# TeslaBMS_Shield_3.net
KiCad netlist of a schematic drawn in EAGLE
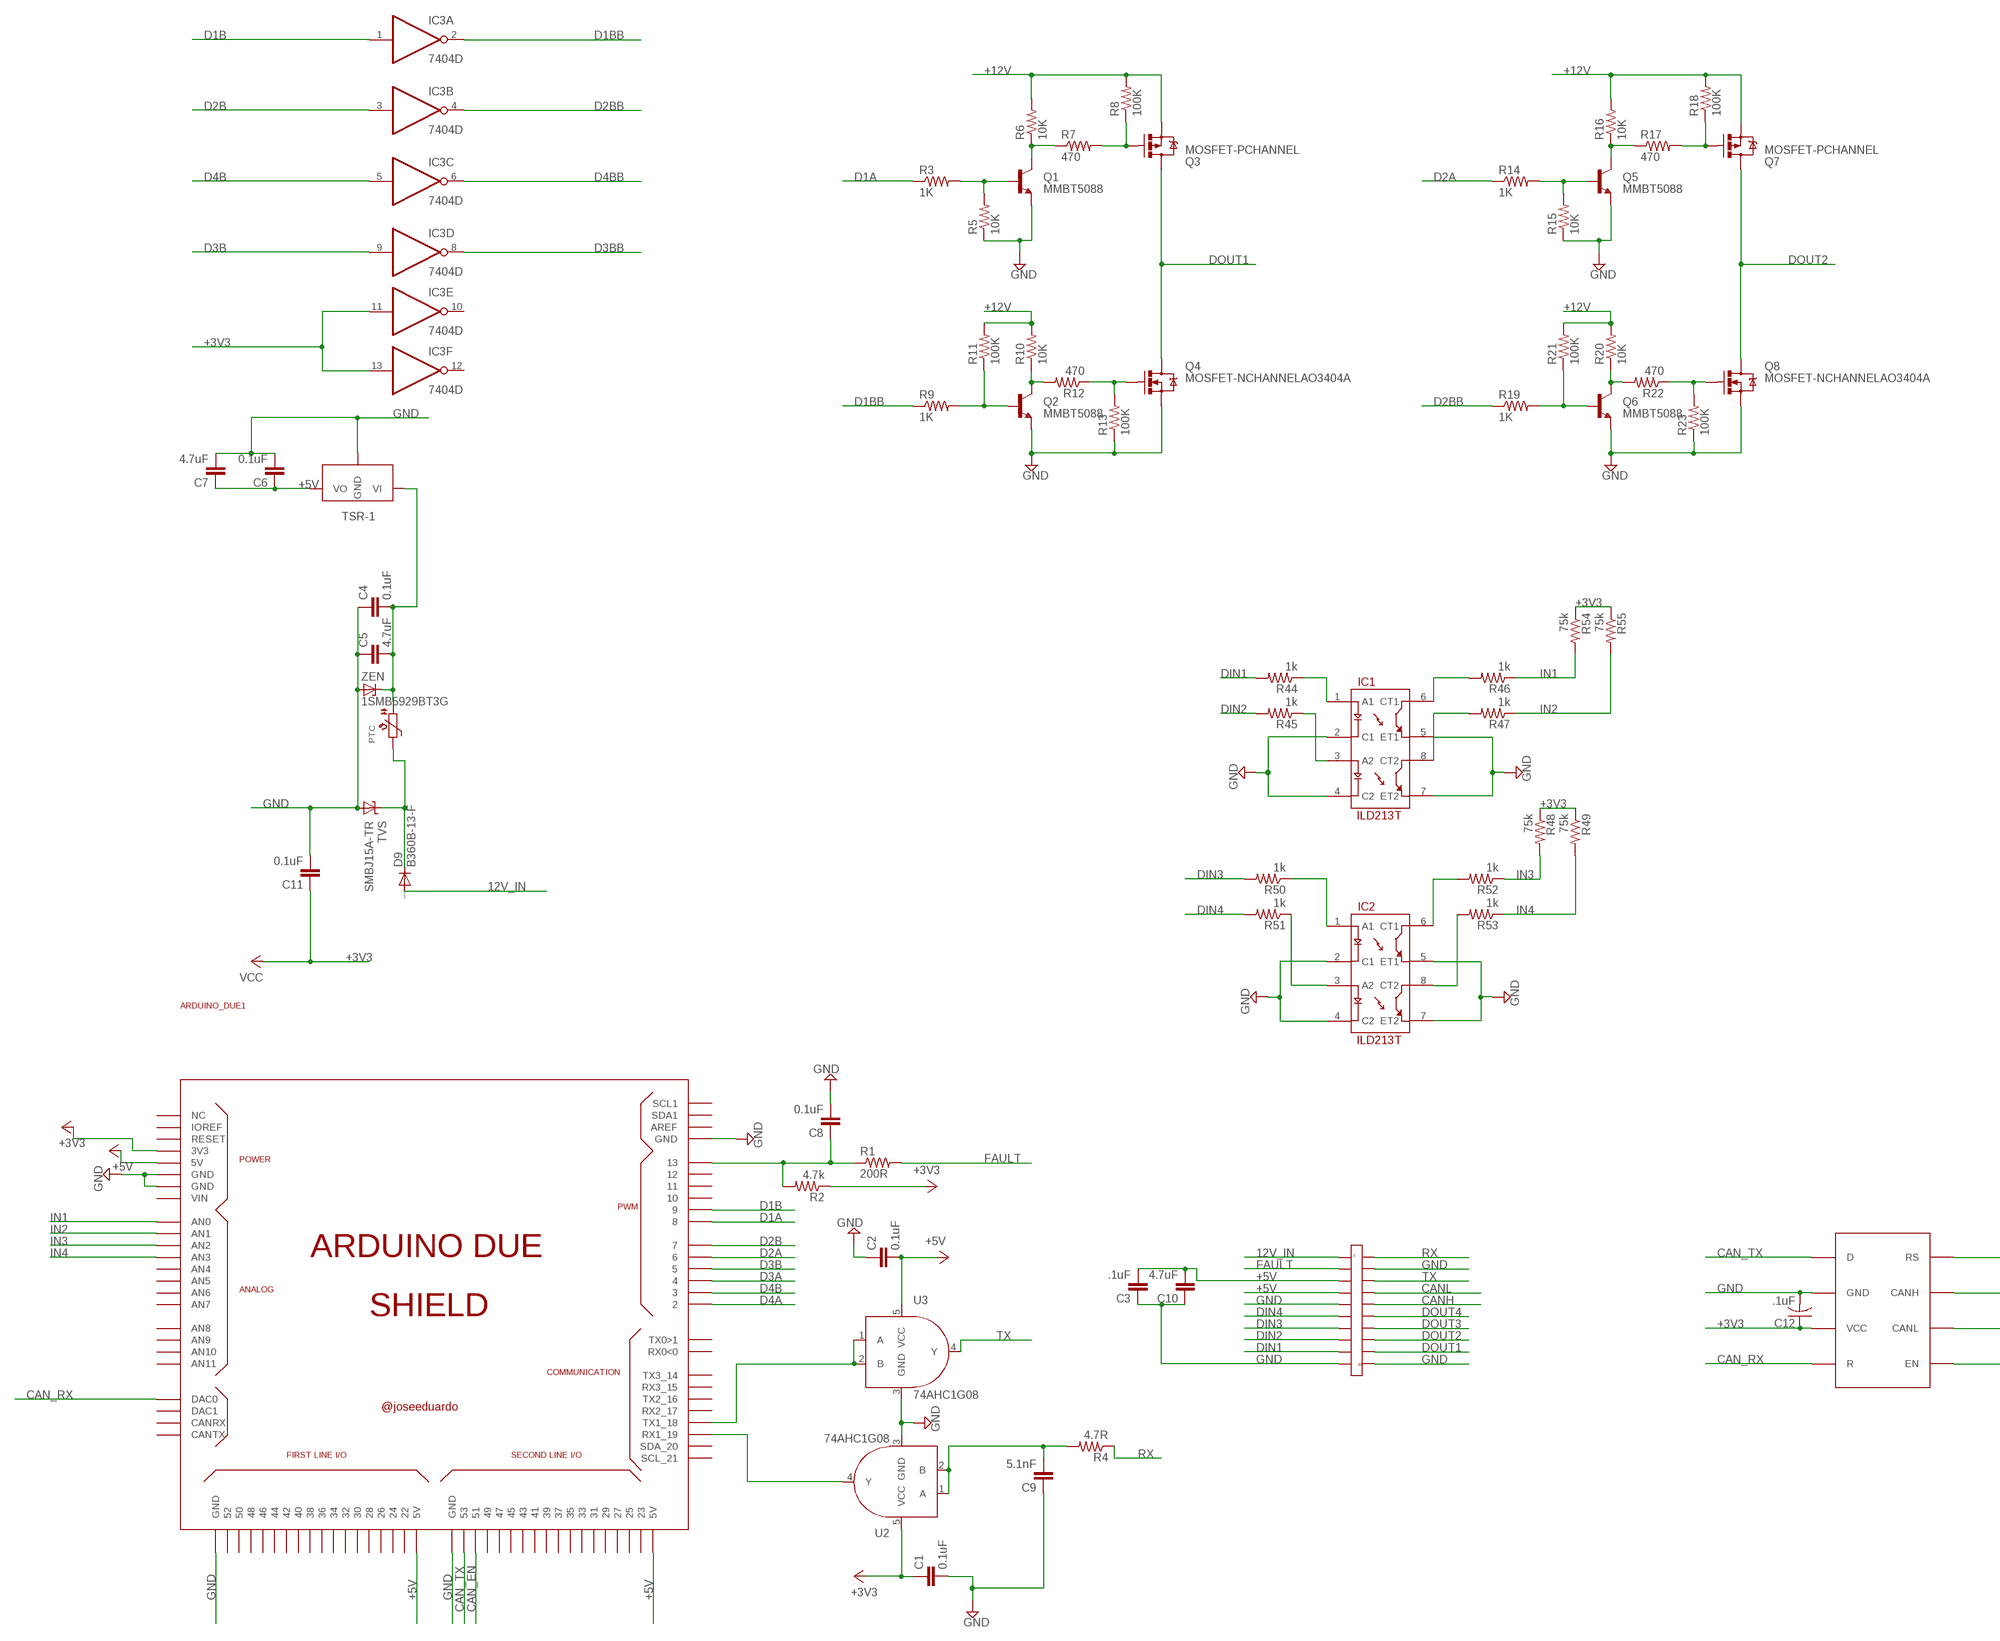
[diagram p0: schematic, sheet 1, part 1 of 2]
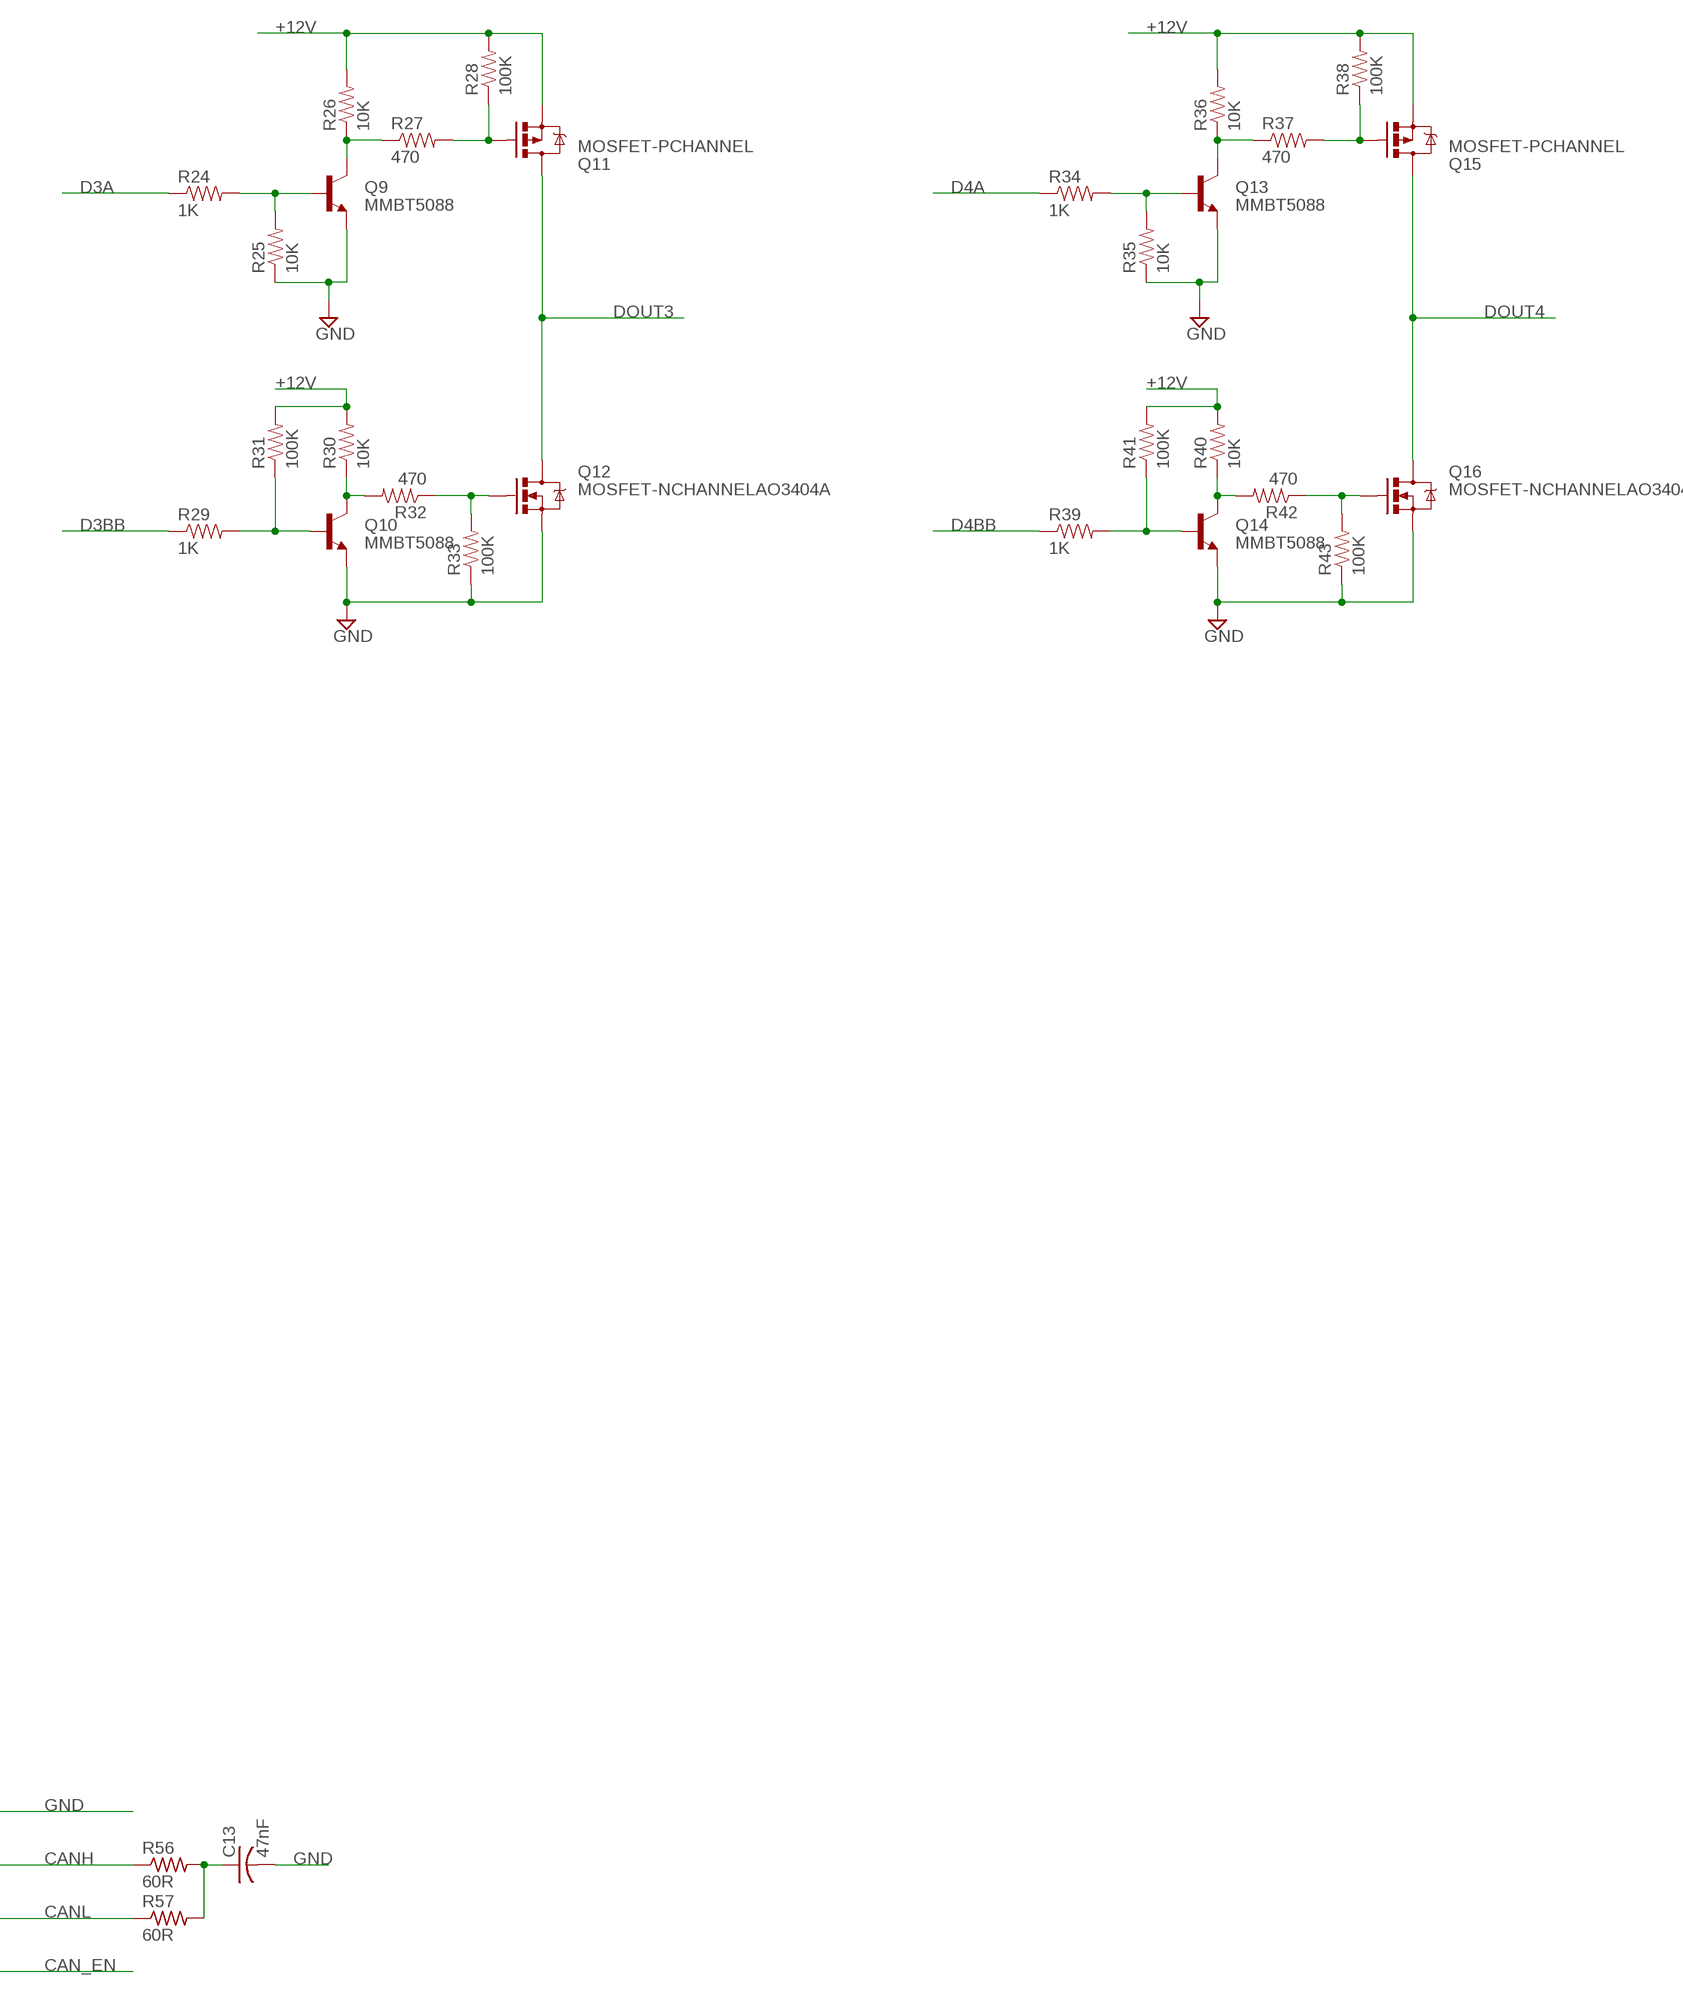
[diagram p1: schematic, sheet 1, part 2 of 2]

(export (version "E")
  (design (tool "Eeschema 10.0.6"))
  (components
    (comp (ref "ARDUINO_DUE1")
      (value "ARDUINO_DUE_SHIELD")
      (footprint "eagle-import:ARDUINO_DUE_SHIELD")
      (libsource (lib "eagle-import") (part "ARDUINO_DUE_SHIELD"))
    )
    (comp (ref "C1")
      (value "0.1uF")
      (footprint "eagle-import:0603-CAP")
      (libsource (lib "eagle-import") (part "CAP0603-CAP"))
    )
    (comp (ref "C2")
      (value "0.1uF")
      (footprint "eagle-import:0603-CAP")
      (libsource (lib "eagle-import") (part "CAP0603-CAP"))
    )
    (comp (ref "C3")
      (value ".1uF")
      (footprint "eagle-import:0603-CAP")
      (libsource (lib "eagle-import") (part "CAP0603-CAP"))
    )
    (comp (ref "C4")
      (value "0.1uF")
      (footprint "eagle-import:0805")
      (libsource (lib "eagle-import") (part "CAP0805"))
    )
    (comp (ref "C5")
      (value "4.7uF")
      (footprint "eagle-import:0805")
      (libsource (lib "eagle-import") (part "CAP0805"))
    )
    (comp (ref "C6")
      (value "0.1uF")
      (footprint "eagle-import:0805")
      (libsource (lib "eagle-import") (part "CAP0805"))
    )
    (comp (ref "C7")
      (value "4.7uF")
      (footprint "eagle-import:0805")
      (libsource (lib "eagle-import") (part "CAP0805"))
    )
    (comp (ref "C8")
      (value "0.1uF")
      (footprint "eagle-import:0603-CAP")
      (libsource (lib "eagle-import") (part "CAP0603-CAP"))
    )
    (comp (ref "C9")
      (value "5.1nF")
      (footprint "eagle-import:0603-CAP")
      (libsource (lib "eagle-import") (part "CAP0603-CAP"))
    )
    (comp (ref "C10")
      (value "4.7uF")
      (footprint "eagle-import:0603-CAP")
      (libsource (lib "eagle-import") (part "CAP0603-CAP"))
    )
    (comp (ref "C11")
      (value "0.1uF")
      (footprint "eagle-import:0805")
      (libsource (lib "eagle-import") (part "CAP0805"))
    )
    (comp (ref "C12")
      (value ".1uF")
      (footprint "eagle-import:C0603")
      (libsource (lib "eagle-import") (part "C-USC0603"))
    )
    (comp (ref "C13")
      (value "47nF")
      (footprint "eagle-import:C0805")
      (libsource (lib "eagle-import") (part "C-USC0805"))
    )
    (comp (ref "D9")
      (value "B360B-13-F")
      (footprint "eagle-import:SMB")
      (libsource (lib "eagle-import") (part "DIODE-SMB"))
    )
    (comp (ref "IC1")
      (value "ILD213T")
      (footprint "eagle-import:SO08")
      (libsource (lib "eagle-import") (part "ILD213T"))
    )
    (comp (ref "IC2")
      (value "ILD213T")
      (footprint "eagle-import:SO08")
      (libsource (lib "eagle-import") (part "ILD213T"))
    )
    (comp (ref "IC3")
      (value "7404D")
      (footprint "eagle-import:SO14")
      (libsource (lib "eagle-import") (part "7404D"))
    )
    (comp (ref "PTC")
      (value "PTC1812")
      (footprint "eagle-import:PTC1812")
      (libsource (lib "eagle-import") (part "PTC1812"))
    )
    (comp (ref "Q1")
      (value "MMBT5088")
      (footprint "eagle-import:SOT23-3")
      (libsource (lib "eagle-import") (part "TRANSISTOR_NPNMMBT5088"))
    )
    (comp (ref "Q2")
      (value "MMBT5088")
      (footprint "eagle-import:SOT23-3")
      (libsource (lib "eagle-import") (part "TRANSISTOR_NPNMMBT5088"))
    )
    (comp (ref "Q3")
      (value "MOSFET-PCHANNEL")
      (footprint "eagle-import:SOT23-3")
      (libsource (lib "eagle-import") (part "MOSFET-PCHANNEL"))
    )
    (comp (ref "Q4")
      (value "MOSFET-NCHANNELAO3404A")
      (footprint "eagle-import:SOT23-3")
      (libsource (lib "eagle-import") (part "MOSFET-NCHANNELAO3404A"))
    )
    (comp (ref "Q5")
      (value "MMBT5088")
      (footprint "eagle-import:SOT23-3")
      (libsource (lib "eagle-import") (part "TRANSISTOR_NPNMMBT5088"))
    )
    (comp (ref "Q6")
      (value "MMBT5088")
      (footprint "eagle-import:SOT23-3")
      (libsource (lib "eagle-import") (part "TRANSISTOR_NPNMMBT5088"))
    )
    (comp (ref "Q7")
      (value "MOSFET-PCHANNEL")
      (footprint "eagle-import:SOT23-3")
      (libsource (lib "eagle-import") (part "MOSFET-PCHANNEL"))
    )
    (comp (ref "Q8")
      (value "MOSFET-NCHANNELAO3404A")
      (footprint "eagle-import:SOT23-3")
      (libsource (lib "eagle-import") (part "MOSFET-NCHANNELAO3404A"))
    )
    (comp (ref "Q9")
      (value "MMBT5088")
      (footprint "eagle-import:SOT23-3")
      (libsource (lib "eagle-import") (part "TRANSISTOR_NPNMMBT5088"))
    )
    (comp (ref "Q10")
      (value "MMBT5088")
      (footprint "eagle-import:SOT23-3")
      (libsource (lib "eagle-import") (part "TRANSISTOR_NPNMMBT5088"))
    )
    (comp (ref "Q11")
      (value "MOSFET-PCHANNEL")
      (footprint "eagle-import:SOT23-3")
      (libsource (lib "eagle-import") (part "MOSFET-PCHANNEL"))
    )
    (comp (ref "Q12")
      (value "MOSFET-NCHANNELAO3404A")
      (footprint "eagle-import:SOT23-3")
      (libsource (lib "eagle-import") (part "MOSFET-NCHANNELAO3404A"))
    )
    (comp (ref "Q13")
      (value "MMBT5088")
      (footprint "eagle-import:SOT23-3")
      (libsource (lib "eagle-import") (part "TRANSISTOR_NPNMMBT5088"))
    )
    (comp (ref "Q14")
      (value "MMBT5088")
      (footprint "eagle-import:SOT23-3")
      (libsource (lib "eagle-import") (part "TRANSISTOR_NPNMMBT5088"))
    )
    (comp (ref "Q15")
      (value "MOSFET-PCHANNEL")
      (footprint "eagle-import:SOT23-3")
      (libsource (lib "eagle-import") (part "MOSFET-PCHANNEL"))
    )
    (comp (ref "Q16")
      (value "MOSFET-NCHANNELAO3404A")
      (footprint "eagle-import:SOT23-3")
      (libsource (lib "eagle-import") (part "MOSFET-NCHANNELAO3404A"))
    )
    (comp (ref "R1")
      (value "200R")
      (footprint "eagle-import:0603-RES")
      (libsource (lib "eagle-import") (part "RESISTOR0603-RES"))
    )
    (comp (ref "R2")
      (value "4.7k")
      (footprint "eagle-import:0603-RES")
      (libsource (lib "eagle-import") (part "RESISTOR0603-RES"))
    )
    (comp (ref "R3")
      (value "1K")
      (footprint "eagle-import:0402-RES")
      (libsource (lib "eagle-import") (part "RESISTOR0402"))
    )
    (comp (ref "R4")
      (value "4.7R")
      (footprint "eagle-import:0603-RES")
      (libsource (lib "eagle-import") (part "RESISTOR0603-RES"))
    )
    (comp (ref "R5")
      (value "10K")
      (footprint "eagle-import:0402-RES")
      (libsource (lib "eagle-import") (part "RESISTOR0402"))
    )
    (comp (ref "R6")
      (value "10K")
      (footprint "eagle-import:0402-RES")
      (libsource (lib "eagle-import") (part "RESISTOR0402"))
    )
    (comp (ref "R7")
      (value "470")
      (footprint "eagle-import:0402-RES")
      (libsource (lib "eagle-import") (part "RESISTOR0402"))
    )
    (comp (ref "R8")
      (value "100K")
      (footprint "eagle-import:0402-RES")
      (libsource (lib "eagle-import") (part "RESISTOR0402"))
    )
    (comp (ref "R9")
      (value "1K")
      (footprint "eagle-import:0402-RES")
      (libsource (lib "eagle-import") (part "RESISTOR0402"))
    )
    (comp (ref "R10")
      (value "10K")
      (footprint "eagle-import:0402-RES")
      (libsource (lib "eagle-import") (part "RESISTOR0402"))
    )
    (comp (ref "R11")
      (value "100K")
      (footprint "eagle-import:0402-RES")
      (libsource (lib "eagle-import") (part "RESISTOR0402"))
    )
    (comp (ref "R12")
      (value "470")
      (footprint "eagle-import:0402-RES")
      (libsource (lib "eagle-import") (part "RESISTOR0402"))
    )
    (comp (ref "R13")
      (value "100K")
      (footprint "eagle-import:0402-RES")
      (libsource (lib "eagle-import") (part "RESISTOR0402"))
    )
    (comp (ref "R14")
      (value "1K")
      (footprint "eagle-import:0402-RES")
      (libsource (lib "eagle-import") (part "RESISTOR0402"))
    )
    (comp (ref "R15")
      (value "10K")
      (footprint "eagle-import:0402-RES")
      (libsource (lib "eagle-import") (part "RESISTOR0402"))
    )
    (comp (ref "R16")
      (value "10K")
      (footprint "eagle-import:0402-RES")
      (libsource (lib "eagle-import") (part "RESISTOR0402"))
    )
    (comp (ref "R17")
      (value "470")
      (footprint "eagle-import:0402-RES")
      (libsource (lib "eagle-import") (part "RESISTOR0402"))
    )
    (comp (ref "R18")
      (value "100K")
      (footprint "eagle-import:0402-RES")
      (libsource (lib "eagle-import") (part "RESISTOR0402"))
    )
    (comp (ref "R19")
      (value "1K")
      (footprint "eagle-import:0402-RES")
      (libsource (lib "eagle-import") (part "RESISTOR0402"))
    )
    (comp (ref "R20")
      (value "10K")
      (footprint "eagle-import:0402-RES")
      (libsource (lib "eagle-import") (part "RESISTOR0402"))
    )
    (comp (ref "R21")
      (value "100K")
      (footprint "eagle-import:0402-RES")
      (libsource (lib "eagle-import") (part "RESISTOR0402"))
    )
    (comp (ref "R22")
      (value "470")
      (footprint "eagle-import:0402-RES")
      (libsource (lib "eagle-import") (part "RESISTOR0402"))
    )
    (comp (ref "R23")
      (value "100K")
      (footprint "eagle-import:0402-RES")
      (libsource (lib "eagle-import") (part "RESISTOR0402"))
    )
    (comp (ref "R24")
      (value "1K")
      (footprint "eagle-import:0402-RES")
      (libsource (lib "eagle-import") (part "RESISTOR0402"))
    )
    (comp (ref "R25")
      (value "10K")
      (footprint "eagle-import:0402-RES")
      (libsource (lib "eagle-import") (part "RESISTOR0402"))
    )
    (comp (ref "R26")
      (value "10K")
      (footprint "eagle-import:0402-RES")
      (libsource (lib "eagle-import") (part "RESISTOR0402"))
    )
    (comp (ref "R27")
      (value "470")
      (footprint "eagle-import:0402-RES")
      (libsource (lib "eagle-import") (part "RESISTOR0402"))
    )
    (comp (ref "R28")
      (value "100K")
      (footprint "eagle-import:0402-RES")
      (libsource (lib "eagle-import") (part "RESISTOR0402"))
    )
    (comp (ref "R29")
      (value "1K")
      (footprint "eagle-import:0402-RES")
      (libsource (lib "eagle-import") (part "RESISTOR0402"))
    )
    (comp (ref "R30")
      (value "10K")
      (footprint "eagle-import:0402-RES")
      (libsource (lib "eagle-import") (part "RESISTOR0402"))
    )
    (comp (ref "R31")
      (value "100K")
      (footprint "eagle-import:0402-RES")
      (libsource (lib "eagle-import") (part "RESISTOR0402"))
    )
    (comp (ref "R32")
      (value "470")
      (footprint "eagle-import:0402-RES")
      (libsource (lib "eagle-import") (part "RESISTOR0402"))
    )
    (comp (ref "R33")
      (value "100K")
      (footprint "eagle-import:0402-RES")
      (libsource (lib "eagle-import") (part "RESISTOR0402"))
    )
    (comp (ref "R34")
      (value "1K")
      (footprint "eagle-import:0402-RES")
      (libsource (lib "eagle-import") (part "RESISTOR0402"))
    )
    (comp (ref "R35")
      (value "10K")
      (footprint "eagle-import:0402-RES")
      (libsource (lib "eagle-import") (part "RESISTOR0402"))
    )
    (comp (ref "R36")
      (value "10K")
      (footprint "eagle-import:0402-RES")
      (libsource (lib "eagle-import") (part "RESISTOR0402"))
    )
    (comp (ref "R37")
      (value "470")
      (footprint "eagle-import:0402-RES")
      (libsource (lib "eagle-import") (part "RESISTOR0402"))
    )
    (comp (ref "R38")
      (value "100K")
      (footprint "eagle-import:0402-RES")
      (libsource (lib "eagle-import") (part "RESISTOR0402"))
    )
    (comp (ref "R39")
      (value "1K")
      (footprint "eagle-import:0402-RES")
      (libsource (lib "eagle-import") (part "RESISTOR0402"))
    )
    (comp (ref "R40")
      (value "10K")
      (footprint "eagle-import:0402-RES")
      (libsource (lib "eagle-import") (part "RESISTOR0402"))
    )
    (comp (ref "R41")
      (value "100K")
      (footprint "eagle-import:0402-RES")
      (libsource (lib "eagle-import") (part "RESISTOR0402"))
    )
    (comp (ref "R42")
      (value "470")
      (footprint "eagle-import:0402-RES")
      (libsource (lib "eagle-import") (part "RESISTOR0402"))
    )
    (comp (ref "R43")
      (value "100K")
      (footprint "eagle-import:0402-RES")
      (libsource (lib "eagle-import") (part "RESISTOR0402"))
    )
    (comp (ref "R44")
      (value "1k")
      (footprint "eagle-import:0603-RES")
      (libsource (lib "eagle-import") (part "RESISTOR0603-RES"))
    )
    (comp (ref "R45")
      (value "1k")
      (footprint "eagle-import:0603-RES")
      (libsource (lib "eagle-import") (part "RESISTOR0603-RES"))
    )
    (comp (ref "R46")
      (value "1k")
      (footprint "eagle-import:0603-RES")
      (libsource (lib "eagle-import") (part "RESISTOR0603-RES"))
    )
    (comp (ref "R47")
      (value "1k")
      (footprint "eagle-import:0603-RES")
      (libsource (lib "eagle-import") (part "RESISTOR0603-RES"))
    )
    (comp (ref "R48")
      (value "75k")
      (footprint "eagle-import:0603-RES")
      (libsource (lib "eagle-import") (part "RESISTOR0603-RES"))
    )
    (comp (ref "R49")
      (value "75k")
      (footprint "eagle-import:0603-RES")
      (libsource (lib "eagle-import") (part "RESISTOR0603-RES"))
    )
    (comp (ref "R50")
      (value "1k")
      (footprint "eagle-import:0603-RES")
      (libsource (lib "eagle-import") (part "RESISTOR0603-RES"))
    )
    (comp (ref "R51")
      (value "1k")
      (footprint "eagle-import:0603-RES")
      (libsource (lib "eagle-import") (part "RESISTOR0603-RES"))
    )
    (comp (ref "R52")
      (value "1k")
      (footprint "eagle-import:0603-RES")
      (libsource (lib "eagle-import") (part "RESISTOR0603-RES"))
    )
    (comp (ref "R53")
      (value "1k")
      (footprint "eagle-import:0603-RES")
      (libsource (lib "eagle-import") (part "RESISTOR0603-RES"))
    )
    (comp (ref "R54")
      (value "75k")
      (footprint "eagle-import:0603-RES")
      (libsource (lib "eagle-import") (part "RESISTOR0603-RES"))
    )
    (comp (ref "R55")
      (value "75k")
      (footprint "eagle-import:0603-RES")
      (libsource (lib "eagle-import") (part "RESISTOR0603-RES"))
    )
    (comp (ref "R56")
      (value "60R")
      (footprint "eagle-import:M0805")
      (libsource (lib "eagle-import") (part "R-US_M0805"))
    )
    (comp (ref "R57")
      (value "60R")
      (footprint "eagle-import:M0805")
      (libsource (lib "eagle-import") (part "R-US_M0805"))
    )
    (comp (ref "TVS")
      (value "SMBJ15A-TR")
      (footprint "eagle-import:SMBJ")
      (libsource (lib "eagle-import") (part "SUPPRESSOR-SMBJ"))
    )
    (comp (ref "U$2")
      (value "VAL-U-LOK-20PIN")
      (footprint "eagle-import:VALULOK-20")
      (libsource (lib "eagle-import") (part "VAL-U-LOK-20PIN"))
    )
    (comp (ref "U1")
      (value "SN65HVD234")
      (footprint "eagle-import:SOIC8")
      (libsource (lib "eagle-import") (part "SN65HVD234"))
    )
    (comp (ref "U2")
      (value "74AHC1G08")
      (footprint "eagle-import:SOT353")
      (libsource (lib "eagle-import") (part "74AHC1G08"))
    )
    (comp (ref "U3")
      (value "74AHC1G08")
      (footprint "eagle-import:SOT353")
      (libsource (lib "eagle-import") (part "74AHC1G08"))
    )
    (comp (ref "U9")
      (value "TSR-1")
      (footprint "eagle-import:TSR-1")
      (libsource (lib "eagle-import") (part "TSR-1"))
    )
    (comp (ref "ZEN")
      (value "1SMB5929BT3G")
      (footprint "eagle-import:SMB")
      (libsource (lib "eagle-import") (part "ZENER-DIODESMB"))
    )
  )
  (nets
    (net (code "1") (name "+3V3") (class "Default")
      (node (ref "ARDUINO_DUE1") (pin "3V3") (pinfunction "3V3_3V3") (pintype "bidirectional"))
      (node (ref "C1") (pin "1") (pinfunction "1_1") (pintype "passive"))
      (node (ref "C11") (pin "1") (pinfunction "1_1") (pintype "passive"))
      (node (ref "C12") (pin "1") (pinfunction "1_1") (pintype "passive"))
      (node (ref "IC3") (pin "11") (pinfunction "I_11") (pintype "input"))
      (node (ref "IC3") (pin "13") (pinfunction "I_13") (pintype "input"))
      (node (ref "R2") (pin "1") (pinfunction "1_1") (pintype "passive"))
      (node (ref "R48") (pin "1") (pinfunction "1_1") (pintype "passive"))
      (node (ref "R49") (pin "1") (pinfunction "1_1") (pintype "passive"))
      (node (ref "R54") (pin "1") (pinfunction "1_1") (pintype "passive"))
      (node (ref "R55") (pin "1") (pinfunction "1_1") (pintype "passive"))
      (node (ref "U1") (pin "PIN3") (pinfunction "VCC_PIN3") (pintype "bidirectional"))
      (node (ref "U2") (pin "5") (pinfunction "VCC_5") (pintype "bidirectional"))
    )
    (net (code "2") (name "+5V") (class "Default")
      (node (ref "ARDUINO_DUE1") (pin "5V0") (pinfunction "5V_5V0") (pintype "bidirectional"))
      (node (ref "ARDUINO_DUE1") (pin "5V0_1") (pinfunction "5V_5V0_1") (pintype "bidirectional"))
      (node (ref "ARDUINO_DUE1") (pin "5V0_2") (pinfunction "5V_5V0_2") (pintype "bidirectional"))
      (node (ref "C10") (pin "2") (pinfunction "2_2") (pintype "passive"))
      (node (ref "C2") (pin "2") (pinfunction "2_2") (pintype "passive"))
      (node (ref "C3") (pin "2") (pinfunction "2_2") (pintype "passive"))
      (node (ref "C6") (pin "1") (pinfunction "1_1") (pintype "passive"))
      (node (ref "C7") (pin "1") (pinfunction "1_1") (pintype "passive"))
      (node (ref "U$2") (pin "P$3") (pinfunction "P$3_P$3") (pintype "bidirectional"))
      (node (ref "U$2") (pin "P$4") (pinfunction "P$4_P$4") (pintype "bidirectional"))
      (node (ref "U3") (pin "5") (pinfunction "VCC_5") (pintype "bidirectional"))
      (node (ref "U9") (pin "P$3") (pinfunction "VO_P$3") (pintype "bidirectional"))
    )
    (net (code "3") (name "/+12V") (class "Default")
      (node (ref "C4") (pin "2") (pinfunction "2_2") (pintype "passive"))
      (node (ref "C5") (pin "2") (pinfunction "2_2") (pintype "passive"))
      (node (ref "PTC") (pin "P$1") (pinfunction "1_P$1") (pintype "passive"))
      (node (ref "Q11") (pin "2") (pinfunction "S_2") (pintype "passive"))
      (node (ref "Q15") (pin "2") (pinfunction "S_2") (pintype "passive"))
      (node (ref "Q3") (pin "2") (pinfunction "S_2") (pintype "passive"))
      (node (ref "Q7") (pin "2") (pinfunction "S_2") (pintype "passive"))
      (node (ref "R10") (pin "2") (pinfunction "2_2") (pintype "passive"))
      (node (ref "R11") (pin "2") (pinfunction "2_2") (pintype "passive"))
      (node (ref "R16") (pin "2") (pinfunction "2_2") (pintype "passive"))
      (node (ref "R18") (pin "2") (pinfunction "2_2") (pintype "passive"))
      (node (ref "R20") (pin "2") (pinfunction "2_2") (pintype "passive"))
      (node (ref "R21") (pin "2") (pinfunction "2_2") (pintype "passive"))
      (node (ref "R26") (pin "2") (pinfunction "2_2") (pintype "passive"))
      (node (ref "R28") (pin "2") (pinfunction "2_2") (pintype "passive"))
      (node (ref "R30") (pin "2") (pinfunction "2_2") (pintype "passive"))
      (node (ref "R31") (pin "2") (pinfunction "2_2") (pintype "passive"))
      (node (ref "R36") (pin "2") (pinfunction "2_2") (pintype "passive"))
      (node (ref "R38") (pin "2") (pinfunction "2_2") (pintype "passive"))
      (node (ref "R40") (pin "2") (pinfunction "2_2") (pintype "passive"))
      (node (ref "R41") (pin "2") (pinfunction "2_2") (pintype "passive"))
      (node (ref "R6") (pin "2") (pinfunction "2_2") (pintype "passive"))
      (node (ref "R8") (pin "2") (pinfunction "2_2") (pintype "passive"))
      (node (ref "U9") (pin "P$1") (pinfunction "VI_P$1") (pintype "bidirectional"))
      (node (ref "ZEN") (pin "C") (pinfunction "C_C") (pintype "passive"))
    )
    (net (code "4") (name "/12V_IN") (class "Default")
      (node (ref "D9") (pin "A") (pinfunction "A_A") (pintype "passive"))
      (node (ref "U$2") (pin "P$1") (pinfunction "P$1_P$1") (pintype "bidirectional"))
    )
    (net (code "5") (name "/CANH") (class "Default")
      (node (ref "R56") (pin "1") (pinfunction "1_1") (pintype "passive"))
      (node (ref "U$2") (pin "P$15") (pinfunction "P$15_P$15") (pintype "bidirectional"))
      (node (ref "U1") (pin "PIN7") (pinfunction "CANH_PIN7") (pintype "bidirectional"))
    )
    (net (code "6") (name "/CANL") (class "Default")
      (node (ref "R57") (pin "1") (pinfunction "1_1") (pintype "passive"))
      (node (ref "U$2") (pin "P$14") (pinfunction "P$14_P$14") (pintype "bidirectional"))
      (node (ref "U1") (pin "PIN6") (pinfunction "CANL_PIN6") (pintype "bidirectional"))
    )
    (net (code "7") (name "/CAN_EN") (class "Default")
      (node (ref "ARDUINO_DUE1") (pin "51") (pinfunction "51_51") (pintype "bidirectional"))
      (node (ref "U1") (pin "PIN5") (pinfunction "EN_PIN5") (pintype "bidirectional"))
    )
    (net (code "8") (name "/CAN_RX") (class "Default")
      (node (ref "ARDUINO_DUE1") (pin "DAC0") (pinfunction "DAC0_DAC0") (pintype "bidirectional"))
      (node (ref "U1") (pin "PIN4") (pinfunction "R_PIN4") (pintype "bidirectional"))
    )
    (net (code "9") (name "/CAN_TX") (class "Default")
      (node (ref "ARDUINO_DUE1") (pin "53") (pinfunction "53_53") (pintype "bidirectional"))
      (node (ref "U1") (pin "PIN1") (pinfunction "D_PIN1") (pintype "bidirectional"))
    )
    (net (code "10") (name "/D1A") (class "Default")
      (node (ref "ARDUINO_DUE1") (pin "8") (pinfunction "8_8") (pintype "bidirectional"))
      (node (ref "R3") (pin "1") (pinfunction "1_1") (pintype "passive"))
    )
    (net (code "11") (name "/D1B") (class "Default")
      (node (ref "ARDUINO_DUE1") (pin "9") (pinfunction "9_9") (pintype "bidirectional"))
      (node (ref "IC3") (pin "1") (pinfunction "I_1") (pintype "input"))
    )
    (net (code "12") (name "/D1BB") (class "Default")
      (node (ref "IC3") (pin "2") (pinfunction "O_2") (pintype "output"))
      (node (ref "R9") (pin "1") (pinfunction "1_1") (pintype "passive"))
    )
    (net (code "13") (name "/D2A") (class "Default")
      (node (ref "ARDUINO_DUE1") (pin "6") (pinfunction "6_6") (pintype "bidirectional"))
      (node (ref "R14") (pin "1") (pinfunction "1_1") (pintype "passive"))
    )
    (net (code "14") (name "/D2B") (class "Default")
      (node (ref "ARDUINO_DUE1") (pin "7") (pinfunction "7_7") (pintype "bidirectional"))
      (node (ref "IC3") (pin "3") (pinfunction "I_3") (pintype "input"))
    )
    (net (code "15") (name "/D2BB") (class "Default")
      (node (ref "IC3") (pin "4") (pinfunction "O_4") (pintype "output"))
      (node (ref "R19") (pin "1") (pinfunction "1_1") (pintype "passive"))
    )
    (net (code "16") (name "/D3A") (class "Default")
      (node (ref "ARDUINO_DUE1") (pin "4") (pinfunction "4_4") (pintype "bidirectional"))
      (node (ref "R24") (pin "1") (pinfunction "1_1") (pintype "passive"))
    )
    (net (code "17") (name "/D3B") (class "Default")
      (node (ref "ARDUINO_DUE1") (pin "5") (pinfunction "5_5") (pintype "bidirectional"))
      (node (ref "IC3") (pin "9") (pinfunction "I_9") (pintype "input"))
    )
    (net (code "18") (name "/D3BB") (class "Default")
      (node (ref "IC3") (pin "8") (pinfunction "O_8") (pintype "output"))
      (node (ref "R29") (pin "1") (pinfunction "1_1") (pintype "passive"))
    )
    (net (code "19") (name "/D4A") (class "Default")
      (node (ref "ARDUINO_DUE1") (pin "2") (pinfunction "2_2") (pintype "bidirectional"))
      (node (ref "R34") (pin "1") (pinfunction "1_1") (pintype "passive"))
    )
    (net (code "20") (name "/D4B") (class "Default")
      (node (ref "ARDUINO_DUE1") (pin "3") (pinfunction "3_3") (pintype "bidirectional"))
      (node (ref "IC3") (pin "5") (pinfunction "I_5") (pintype "input"))
    )
    (net (code "21") (name "/D4BB") (class "Default")
      (node (ref "IC3") (pin "6") (pinfunction "O_6") (pintype "output"))
      (node (ref "R39") (pin "1") (pinfunction "1_1") (pintype "passive"))
    )
    (net (code "22") (name "/DIN1") (class "Default")
      (node (ref "R44") (pin "2") (pinfunction "2_2") (pintype "passive"))
      (node (ref "U$2") (pin "P$9") (pinfunction "P$9_P$9") (pintype "bidirectional"))
    )
    (net (code "23") (name "/DIN2") (class "Default")
      (node (ref "R45") (pin "2") (pinfunction "2_2") (pintype "passive"))
      (node (ref "U$2") (pin "P$8") (pinfunction "P$8_P$8") (pintype "bidirectional"))
    )
    (net (code "24") (name "/DIN3") (class "Default")
      (node (ref "R50") (pin "2") (pinfunction "2_2") (pintype "passive"))
      (node (ref "U$2") (pin "P$7") (pinfunction "P$7_P$7") (pintype "bidirectional"))
    )
    (net (code "25") (name "/DIN4") (class "Default")
      (node (ref "R51") (pin "2") (pinfunction "2_2") (pintype "passive"))
      (node (ref "U$2") (pin "P$6") (pinfunction "P$6_P$6") (pintype "bidirectional"))
    )
    (net (code "26") (name "/DOUT1") (class "Default")
      (node (ref "Q3") (pin "3") (pinfunction "D_3") (pintype "passive"))
      (node (ref "Q4") (pin "3") (pinfunction "D_3") (pintype "passive"))
      (node (ref "U$2") (pin "P$19") (pinfunction "P$19_P$19") (pintype "bidirectional"))
    )
    (net (code "27") (name "/DOUT2") (class "Default")
      (node (ref "Q7") (pin "3") (pinfunction "D_3") (pintype "passive"))
      (node (ref "Q8") (pin "3") (pinfunction "D_3") (pintype "passive"))
      (node (ref "U$2") (pin "P$18") (pinfunction "P$18_P$18") (pintype "bidirectional"))
    )
    (net (code "28") (name "/DOUT3") (class "Default")
      (node (ref "Q11") (pin "3") (pinfunction "D_3") (pintype "passive"))
      (node (ref "Q12") (pin "3") (pinfunction "D_3") (pintype "passive"))
      (node (ref "U$2") (pin "P$17") (pinfunction "P$17_P$17") (pintype "bidirectional"))
    )
    (net (code "29") (name "/DOUT4") (class "Default")
      (node (ref "Q15") (pin "3") (pinfunction "D_3") (pintype "passive"))
      (node (ref "Q16") (pin "3") (pinfunction "D_3") (pintype "passive"))
      (node (ref "U$2") (pin "P$16") (pinfunction "P$16_P$16") (pintype "bidirectional"))
    )
    (net (code "30") (name "/FAULT") (class "Default")
      (node (ref "R1") (pin "2") (pinfunction "2_2") (pintype "passive"))
      (node (ref "U$2") (pin "P$2") (pinfunction "P$2_P$2") (pintype "bidirectional"))
    )
    (net (code "31") (name "/IN1") (class "Default")
      (node (ref "ARDUINO_DUE1") (pin "A0") (pinfunction "AN0_A0") (pintype "bidirectional"))
      (node (ref "R46") (pin "1") (pinfunction "1_1") (pintype "passive"))
      (node (ref "R54") (pin "2") (pinfunction "2_2") (pintype "passive"))
    )
    (net (code "32") (name "/IN2") (class "Default")
      (node (ref "ARDUINO_DUE1") (pin "A1") (pinfunction "AN1_A1") (pintype "bidirectional"))
      (node (ref "R47") (pin "1") (pinfunction "1_1") (pintype "passive"))
      (node (ref "R55") (pin "2") (pinfunction "2_2") (pintype "passive"))
    )
    (net (code "33") (name "/IN3") (class "Default")
      (node (ref "ARDUINO_DUE1") (pin "A2") (pinfunction "AN2_A2") (pintype "bidirectional"))
      (node (ref "R48") (pin "2") (pinfunction "2_2") (pintype "passive"))
      (node (ref "R52") (pin "1") (pinfunction "1_1") (pintype "passive"))
    )
    (net (code "34") (name "/IN4") (class "Default")
      (node (ref "ARDUINO_DUE1") (pin "A3") (pinfunction "AN3_A3") (pintype "bidirectional"))
      (node (ref "R49") (pin "2") (pinfunction "2_2") (pintype "passive"))
      (node (ref "R53") (pin "1") (pinfunction "1_1") (pintype "passive"))
    )
    (net (code "35") (name "/RX") (class "Default")
      (node (ref "R4") (pin "1") (pinfunction "1_1") (pintype "passive"))
      (node (ref "U$2") (pin "P$11") (pinfunction "P$11_P$11") (pintype "bidirectional"))
    )
    (net (code "36") (name "/TX") (class "Default")
      (node (ref "U$2") (pin "P$13") (pinfunction "P$13_P$13") (pintype "bidirectional"))
      (node (ref "U3") (pin "4") (pinfunction "Y_4") (pintype "bidirectional"))
    )
    (net (code "37") (name "GND") (class "Default")
      (node (ref "ARDUINO_DUE1") (pin "GND") (pinfunction "GND_GND") (pintype "bidirectional"))
      (node (ref "ARDUINO_DUE1") (pin "GND_1") (pinfunction "GND_GND_1") (pintype "bidirectional"))
      (node (ref "ARDUINO_DUE1") (pin "GND_2") (pinfunction "GND_GND_2") (pintype "bidirectional"))
      (node (ref "ARDUINO_DUE1") (pin "GND_3") (pinfunction "GND_GND_3") (pintype "bidirectional"))
      (node (ref "ARDUINO_DUE1") (pin "GND_4") (pinfunction "GND_GND_4") (pintype "bidirectional"))
      (node (ref "C1") (pin "2") (pinfunction "2_2") (pintype "passive"))
      (node (ref "C10") (pin "1") (pinfunction "1_1") (pintype "passive"))
      (node (ref "C11") (pin "2") (pinfunction "2_2") (pintype "passive"))
      (node (ref "C12") (pin "2") (pinfunction "2_2") (pintype "passive"))
      (node (ref "C13") (pin "2") (pinfunction "2_2") (pintype "passive"))
      (node (ref "C2") (pin "1") (pinfunction "1_1") (pintype "passive"))
      (node (ref "C3") (pin "1") (pinfunction "1_1") (pintype "passive"))
      (node (ref "C4") (pin "1") (pinfunction "1_1") (pintype "passive"))
      (node (ref "C5") (pin "1") (pinfunction "1_1") (pintype "passive"))
      (node (ref "C6") (pin "2") (pinfunction "2_2") (pintype "passive"))
      (node (ref "C7") (pin "2") (pinfunction "2_2") (pintype "passive"))
      (node (ref "C8") (pin "2") (pinfunction "2_2") (pintype "passive"))
      (node (ref "C9") (pin "1") (pinfunction "1_1") (pintype "passive"))
      (node (ref "IC1") (pin "2") (pinfunction "C1_2") (pintype "bidirectional"))
      (node (ref "IC1") (pin "4") (pinfunction "C2_4") (pintype "bidirectional"))
      (node (ref "IC1") (pin "5") (pinfunction "ET1_5") (pintype "bidirectional"))
      (node (ref "IC1") (pin "7") (pinfunction "ET2_7") (pintype "bidirectional"))
      (node (ref "IC2") (pin "2") (pinfunction "C1_2") (pintype "bidirectional"))
      (node (ref "IC2") (pin "4") (pinfunction "C2_4") (pintype "bidirectional"))
      (node (ref "IC2") (pin "5") (pinfunction "ET1_5") (pintype "bidirectional"))
      (node (ref "IC2") (pin "7") (pinfunction "ET2_7") (pintype "bidirectional"))
      (node (ref "Q1") (pin "2") (pinfunction "E_2") (pintype "passive"))
      (node (ref "Q10") (pin "2") (pinfunction "E_2") (pintype "passive"))
      (node (ref "Q12") (pin "2") (pinfunction "S_2") (pintype "passive"))
      (node (ref "Q13") (pin "2") (pinfunction "E_2") (pintype "passive"))
      (node (ref "Q14") (pin "2") (pinfunction "E_2") (pintype "passive"))
      (node (ref "Q16") (pin "2") (pinfunction "S_2") (pintype "passive"))
      (node (ref "Q2") (pin "2") (pinfunction "E_2") (pintype "passive"))
      (node (ref "Q4") (pin "2") (pinfunction "S_2") (pintype "passive"))
      (node (ref "Q5") (pin "2") (pinfunction "E_2") (pintype "passive"))
      (node (ref "Q6") (pin "2") (pinfunction "E_2") (pintype "passive"))
      (node (ref "Q8") (pin "2") (pinfunction "S_2") (pintype "passive"))
      (node (ref "Q9") (pin "2") (pinfunction "E_2") (pintype "passive"))
      (node (ref "R13") (pin "1") (pinfunction "1_1") (pintype "passive"))
      (node (ref "R15") (pin "1") (pinfunction "1_1") (pintype "passive"))
      (node (ref "R23") (pin "1") (pinfunction "1_1") (pintype "passive"))
      (node (ref "R25") (pin "1") (pinfunction "1_1") (pintype "passive"))
      (node (ref "R33") (pin "1") (pinfunction "1_1") (pintype "passive"))
      (node (ref "R35") (pin "1") (pinfunction "1_1") (pintype "passive"))
      (node (ref "R43") (pin "1") (pinfunction "1_1") (pintype "passive"))
      (node (ref "R5") (pin "1") (pinfunction "1_1") (pintype "passive"))
      (node (ref "TVS") (pin "A") (pinfunction "A_A") (pintype "passive"))
      (node (ref "U$2") (pin "P$10") (pinfunction "P$10_P$10") (pintype "bidirectional"))
      (node (ref "U$2") (pin "P$12") (pinfunction "P$12_P$12") (pintype "bidirectional"))
      (node (ref "U$2") (pin "P$20") (pinfunction "P$20_P$20") (pintype "bidirectional"))
      (node (ref "U$2") (pin "P$5") (pinfunction "P$5_P$5") (pintype "bidirectional"))
      (node (ref "U1") (pin "PIN2") (pinfunction "GND_PIN2") (pintype "bidirectional"))
      (node (ref "U1") (pin "PIN8") (pinfunction "RS_PIN8") (pintype "bidirectional"))
      (node (ref "U2") (pin "3") (pinfunction "GND_3") (pintype "bidirectional"))
      (node (ref "U3") (pin "3") (pinfunction "GND_3") (pintype "bidirectional"))
      (node (ref "U9") (pin "P$2") (pinfunction "GND_P$2") (pintype "bidirectional"))
      (node (ref "ZEN") (pin "A") (pinfunction "A_A") (pintype "passive"))
    )
    (net (code "38") (name "Net-(ARDUINO_DUE1-Pad13)") (class "Default")
      (node (ref "ARDUINO_DUE1") (pin "13") (pinfunction "13_13") (pintype "bidirectional"))
      (node (ref "C8") (pin "1") (pinfunction "1_1") (pintype "passive"))
      (node (ref "R1") (pin "1") (pinfunction "1_1") (pintype "passive"))
      (node (ref "R2") (pin "2") (pinfunction "2_2") (pintype "passive"))
    )
    (net (code "39") (name "Net-(ARDUINO_DUE1-RX1_19)") (class "Default")
      (node (ref "ARDUINO_DUE1") (pin "19") (pinfunction "RX1_19_19") (pintype "bidirectional"))
      (node (ref "U2") (pin "4") (pinfunction "Y_4") (pintype "bidirectional"))
    )
    (net (code "40") (name "Net-(ARDUINO_DUE1-TX1_18)") (class "Default")
      (node (ref "ARDUINO_DUE1") (pin "18") (pinfunction "TX1_18_18") (pintype "bidirectional"))
      (node (ref "U3") (pin "1") (pinfunction "A_1") (pintype "bidirectional"))
      (node (ref "U3") (pin "2") (pinfunction "B_2") (pintype "bidirectional"))
    )
    (net (code "41") (name "Net-(C13-Pad1)") (class "Default")
      (node (ref "C13") (pin "1") (pinfunction "1_1") (pintype "passive"))
      (node (ref "R56") (pin "2") (pinfunction "2_2") (pintype "passive"))
      (node (ref "R57") (pin "2") (pinfunction "2_2") (pintype "passive"))
    )
    (net (code "42") (name "Net-(IC1-A1)") (class "Default")
      (node (ref "IC1") (pin "1") (pinfunction "A1_1") (pintype "bidirectional"))
      (node (ref "R44") (pin "1") (pinfunction "1_1") (pintype "passive"))
    )
    (net (code "43") (name "Net-(IC1-A2)") (class "Default")
      (node (ref "IC1") (pin "3") (pinfunction "A2_3") (pintype "bidirectional"))
      (node (ref "R45") (pin "1") (pinfunction "1_1") (pintype "passive"))
    )
    (net (code "44") (name "Net-(IC1-CT1)") (class "Default")
      (node (ref "IC1") (pin "6") (pinfunction "CT1_6") (pintype "bidirectional"))
      (node (ref "R46") (pin "2") (pinfunction "2_2") (pintype "passive"))
    )
    (net (code "45") (name "Net-(IC1-CT2)") (class "Default")
      (node (ref "IC1") (pin "8") (pinfunction "CT2_8") (pintype "bidirectional"))
      (node (ref "R47") (pin "2") (pinfunction "2_2") (pintype "passive"))
    )
    (net (code "46") (name "Net-(IC2-A1)") (class "Default")
      (node (ref "IC2") (pin "1") (pinfunction "A1_1") (pintype "bidirectional"))
      (node (ref "R50") (pin "1") (pinfunction "1_1") (pintype "passive"))
    )
    (net (code "47") (name "Net-(IC2-A2)") (class "Default")
      (node (ref "IC2") (pin "3") (pinfunction "A2_3") (pintype "bidirectional"))
      (node (ref "R51") (pin "1") (pinfunction "1_1") (pintype "passive"))
    )
    (net (code "48") (name "Net-(IC2-CT1)") (class "Default")
      (node (ref "IC2") (pin "6") (pinfunction "CT1_6") (pintype "bidirectional"))
      (node (ref "R52") (pin "2") (pinfunction "2_2") (pintype "passive"))
    )
    (net (code "49") (name "Net-(IC2-CT2)") (class "Default")
      (node (ref "IC2") (pin "8") (pinfunction "CT2_8") (pintype "bidirectional"))
      (node (ref "R53") (pin "2") (pinfunction "2_2") (pintype "passive"))
    )
    (net (code "50") (name "Net-(PTC-2)") (class "Default")
      (node (ref "D9") (pin "C") (pinfunction "C_C") (pintype "passive"))
      (node (ref "PTC") (pin "P$2") (pinfunction "2_P$2") (pintype "passive"))
      (node (ref "TVS") (pin "C") (pinfunction "C_C") (pintype "passive"))
    )
    (net (code "51") (name "Net-(Q1-B)") (class "Default")
      (node (ref "Q1") (pin "1") (pinfunction "B_1") (pintype "passive"))
      (node (ref "R3") (pin "2") (pinfunction "2_2") (pintype "passive"))
      (node (ref "R5") (pin "2") (pinfunction "2_2") (pintype "passive"))
    )
    (net (code "52") (name "Net-(Q1-C)") (class "Default")
      (node (ref "Q1") (pin "3") (pinfunction "C_3") (pintype "passive"))
      (node (ref "R6") (pin "1") (pinfunction "1_1") (pintype "passive"))
      (node (ref "R7") (pin "1") (pinfunction "1_1") (pintype "passive"))
    )
    (net (code "53") (name "Net-(Q2-B)") (class "Default")
      (node (ref "Q2") (pin "1") (pinfunction "B_1") (pintype "passive"))
      (node (ref "R11") (pin "1") (pinfunction "1_1") (pintype "passive"))
      (node (ref "R9") (pin "2") (pinfunction "2_2") (pintype "passive"))
    )
    (net (code "54") (name "Net-(Q2-C)") (class "Default")
      (node (ref "Q2") (pin "3") (pinfunction "C_3") (pintype "passive"))
      (node (ref "R10") (pin "1") (pinfunction "1_1") (pintype "passive"))
      (node (ref "R12") (pin "2") (pinfunction "2_2") (pintype "passive"))
    )
    (net (code "55") (name "Net-(Q3-G)") (class "Default")
      (node (ref "Q3") (pin "1") (pinfunction "G_1") (pintype "passive"))
      (node (ref "R7") (pin "2") (pinfunction "2_2") (pintype "passive"))
      (node (ref "R8") (pin "1") (pinfunction "1_1") (pintype "passive"))
    )
    (net (code "56") (name "Net-(Q4-G)") (class "Default")
      (node (ref "Q4") (pin "1") (pinfunction "G_1") (pintype "passive"))
      (node (ref "R12") (pin "1") (pinfunction "1_1") (pintype "passive"))
      (node (ref "R13") (pin "2") (pinfunction "2_2") (pintype "passive"))
    )
    (net (code "57") (name "Net-(Q5-B)") (class "Default")
      (node (ref "Q5") (pin "1") (pinfunction "B_1") (pintype "passive"))
      (node (ref "R14") (pin "2") (pinfunction "2_2") (pintype "passive"))
      (node (ref "R15") (pin "2") (pinfunction "2_2") (pintype "passive"))
    )
    (net (code "58") (name "Net-(Q5-C)") (class "Default")
      (node (ref "Q5") (pin "3") (pinfunction "C_3") (pintype "passive"))
      (node (ref "R16") (pin "1") (pinfunction "1_1") (pintype "passive"))
      (node (ref "R17") (pin "1") (pinfunction "1_1") (pintype "passive"))
    )
    (net (code "59") (name "Net-(Q6-B)") (class "Default")
      (node (ref "Q6") (pin "1") (pinfunction "B_1") (pintype "passive"))
      (node (ref "R19") (pin "2") (pinfunction "2_2") (pintype "passive"))
      (node (ref "R21") (pin "1") (pinfunction "1_1") (pintype "passive"))
    )
    (net (code "60") (name "Net-(Q6-C)") (class "Default")
      (node (ref "Q6") (pin "3") (pinfunction "C_3") (pintype "passive"))
      (node (ref "R20") (pin "1") (pinfunction "1_1") (pintype "passive"))
      (node (ref "R22") (pin "2") (pinfunction "2_2") (pintype "passive"))
    )
    (net (code "61") (name "Net-(Q7-G)") (class "Default")
      (node (ref "Q7") (pin "1") (pinfunction "G_1") (pintype "passive"))
      (node (ref "R17") (pin "2") (pinfunction "2_2") (pintype "passive"))
      (node (ref "R18") (pin "1") (pinfunction "1_1") (pintype "passive"))
    )
    (net (code "62") (name "Net-(Q8-G)") (class "Default")
      (node (ref "Q8") (pin "1") (pinfunction "G_1") (pintype "passive"))
      (node (ref "R22") (pin "1") (pinfunction "1_1") (pintype "passive"))
      (node (ref "R23") (pin "2") (pinfunction "2_2") (pintype "passive"))
    )
    (net (code "63") (name "Net-(Q9-B)") (class "Default")
      (node (ref "Q9") (pin "1") (pinfunction "B_1") (pintype "passive"))
      (node (ref "R24") (pin "2") (pinfunction "2_2") (pintype "passive"))
      (node (ref "R25") (pin "2") (pinfunction "2_2") (pintype "passive"))
    )
    (net (code "64") (name "Net-(Q9-C)") (class "Default")
      (node (ref "Q9") (pin "3") (pinfunction "C_3") (pintype "passive"))
      (node (ref "R26") (pin "1") (pinfunction "1_1") (pintype "passive"))
      (node (ref "R27") (pin "1") (pinfunction "1_1") (pintype "passive"))
    )
    (net (code "65") (name "Net-(Q10-B)") (class "Default")
      (node (ref "Q10") (pin "1") (pinfunction "B_1") (pintype "passive"))
      (node (ref "R29") (pin "2") (pinfunction "2_2") (pintype "passive"))
      (node (ref "R31") (pin "1") (pinfunction "1_1") (pintype "passive"))
    )
    (net (code "66") (name "Net-(Q10-C)") (class "Default")
      (node (ref "Q10") (pin "3") (pinfunction "C_3") (pintype "passive"))
      (node (ref "R30") (pin "1") (pinfunction "1_1") (pintype "passive"))
      (node (ref "R32") (pin "2") (pinfunction "2_2") (pintype "passive"))
    )
    (net (code "67") (name "Net-(Q11-G)") (class "Default")
      (node (ref "Q11") (pin "1") (pinfunction "G_1") (pintype "passive"))
      (node (ref "R27") (pin "2") (pinfunction "2_2") (pintype "passive"))
      (node (ref "R28") (pin "1") (pinfunction "1_1") (pintype "passive"))
    )
    (net (code "68") (name "Net-(Q12-G)") (class "Default")
      (node (ref "Q12") (pin "1") (pinfunction "G_1") (pintype "passive"))
      (node (ref "R32") (pin "1") (pinfunction "1_1") (pintype "passive"))
      (node (ref "R33") (pin "2") (pinfunction "2_2") (pintype "passive"))
    )
    (net (code "69") (name "Net-(Q13-B)") (class "Default")
      (node (ref "Q13") (pin "1") (pinfunction "B_1") (pintype "passive"))
      (node (ref "R34") (pin "2") (pinfunction "2_2") (pintype "passive"))
      (node (ref "R35") (pin "2") (pinfunction "2_2") (pintype "passive"))
    )
    (net (code "70") (name "Net-(Q13-C)") (class "Default")
      (node (ref "Q13") (pin "3") (pinfunction "C_3") (pintype "passive"))
      (node (ref "R36") (pin "1") (pinfunction "1_1") (pintype "passive"))
      (node (ref "R37") (pin "1") (pinfunction "1_1") (pintype "passive"))
    )
    (net (code "71") (name "Net-(Q14-B)") (class "Default")
      (node (ref "Q14") (pin "1") (pinfunction "B_1") (pintype "passive"))
      (node (ref "R39") (pin "2") (pinfunction "2_2") (pintype "passive"))
      (node (ref "R41") (pin "1") (pinfunction "1_1") (pintype "passive"))
    )
    (net (code "72") (name "Net-(Q14-C)") (class "Default")
      (node (ref "Q14") (pin "3") (pinfunction "C_3") (pintype "passive"))
      (node (ref "R40") (pin "1") (pinfunction "1_1") (pintype "passive"))
      (node (ref "R42") (pin "2") (pinfunction "2_2") (pintype "passive"))
    )
    (net (code "73") (name "Net-(Q15-G)") (class "Default")
      (node (ref "Q15") (pin "1") (pinfunction "G_1") (pintype "passive"))
      (node (ref "R37") (pin "2") (pinfunction "2_2") (pintype "passive"))
      (node (ref "R38") (pin "1") (pinfunction "1_1") (pintype "passive"))
    )
    (net (code "74") (name "Net-(Q16-G)") (class "Default")
      (node (ref "Q16") (pin "1") (pinfunction "G_1") (pintype "passive"))
      (node (ref "R42") (pin "1") (pinfunction "1_1") (pintype "passive"))
      (node (ref "R43") (pin "2") (pinfunction "2_2") (pintype "passive"))
    )
    (net (code "75") (name "Net-(U2-A)") (class "Default")
      (node (ref "C9") (pin "2") (pinfunction "2_2") (pintype "passive"))
      (node (ref "R4") (pin "2") (pinfunction "2_2") (pintype "passive"))
      (node (ref "U2") (pin "1") (pinfunction "A_1") (pintype "bidirectional"))
      (node (ref "U2") (pin "2") (pinfunction "B_2") (pintype "bidirectional"))
    )
    (net (code "76") (name "unconnected-(ARDUINO_DUE1-AN4-PadA4)") (class "Default")
      (node (ref "ARDUINO_DUE1") (pin "A4") (pinfunction "AN4_A4") (pintype "bidirectional"))
    )
    (net (code "77") (name "unconnected-(ARDUINO_DUE1-AN5-PadA5)") (class "Default")
      (node (ref "ARDUINO_DUE1") (pin "A5") (pinfunction "AN5_A5") (pintype "bidirectional"))
    )
    (net (code "78") (name "unconnected-(ARDUINO_DUE1-AN6-PadA6)") (class "Default")
      (node (ref "ARDUINO_DUE1") (pin "A6") (pinfunction "AN6_A6") (pintype "bidirectional"))
    )
    (net (code "79") (name "unconnected-(ARDUINO_DUE1-AN7-PadA7)") (class "Default")
      (node (ref "ARDUINO_DUE1") (pin "A7") (pinfunction "AN7_A7") (pintype "bidirectional"))
    )
    (net (code "80") (name "unconnected-(ARDUINO_DUE1-AN8-PadA8)") (class "Default")
      (node (ref "ARDUINO_DUE1") (pin "A8") (pinfunction "AN8_A8") (pintype "bidirectional"))
    )
    (net (code "81") (name "unconnected-(ARDUINO_DUE1-AN9-PadA9)") (class "Default")
      (node (ref "ARDUINO_DUE1") (pin "A9") (pinfunction "AN9_A9") (pintype "bidirectional"))
    )
    (net (code "82") (name "unconnected-(ARDUINO_DUE1-AN10-PadA10)") (class "Default")
      (node (ref "ARDUINO_DUE1") (pin "A10") (pinfunction "AN10_A10") (pintype "bidirectional"))
    )
    (net (code "83") (name "unconnected-(ARDUINO_DUE1-AN11-PadA11)") (class "Default")
      (node (ref "ARDUINO_DUE1") (pin "A11") (pinfunction "AN11_A11") (pintype "bidirectional"))
    )
    (net (code "84") (name "unconnected-(ARDUINO_DUE1-NC-PadNC_2)") (class "Default")
      (node (ref "ARDUINO_DUE1") (pin "NC_2") (pinfunction "NC_NC_2") (pintype "no_connect"))
    )
    (net (code "85") (name "unconnected-(ARDUINO_DUE1-Pad10)") (class "Default")
      (node (ref "ARDUINO_DUE1") (pin "10") (pinfunction "10_10") (pintype "bidirectional"))
    )
    (net (code "86") (name "unconnected-(ARDUINO_DUE1-Pad11)") (class "Default")
      (node (ref "ARDUINO_DUE1") (pin "11") (pinfunction "11_11") (pintype "bidirectional"))
    )
    (net (code "87") (name "unconnected-(ARDUINO_DUE1-Pad12)") (class "Default")
      (node (ref "ARDUINO_DUE1") (pin "12") (pinfunction "12_12") (pintype "bidirectional"))
    )
    (net (code "88") (name "unconnected-(ARDUINO_DUE1-Pad22)") (class "Default")
      (node (ref "ARDUINO_DUE1") (pin "22") (pinfunction "22_22") (pintype "bidirectional"))
    )
    (net (code "89") (name "unconnected-(ARDUINO_DUE1-Pad23)") (class "Default")
      (node (ref "ARDUINO_DUE1") (pin "23") (pinfunction "23_23") (pintype "bidirectional"))
    )
    (net (code "90") (name "unconnected-(ARDUINO_DUE1-Pad24)") (class "Default")
      (node (ref "ARDUINO_DUE1") (pin "24") (pinfunction "24_24") (pintype "bidirectional"))
    )
    (net (code "91") (name "unconnected-(ARDUINO_DUE1-Pad25)") (class "Default")
      (node (ref "ARDUINO_DUE1") (pin "25") (pinfunction "25_25") (pintype "bidirectional"))
    )
    (net (code "92") (name "unconnected-(ARDUINO_DUE1-Pad26)") (class "Default")
      (node (ref "ARDUINO_DUE1") (pin "26") (pinfunction "26_26") (pintype "bidirectional"))
    )
    (net (code "93") (name "unconnected-(ARDUINO_DUE1-Pad27)") (class "Default")
      (node (ref "ARDUINO_DUE1") (pin "27") (pinfunction "27_27") (pintype "bidirectional"))
    )
    (net (code "94") (name "unconnected-(ARDUINO_DUE1-Pad28)") (class "Default")
      (node (ref "ARDUINO_DUE1") (pin "28") (pinfunction "28_28") (pintype "bidirectional"))
    )
    (net (code "95") (name "unconnected-(ARDUINO_DUE1-Pad29)") (class "Default")
      (node (ref "ARDUINO_DUE1") (pin "29") (pinfunction "29_29") (pintype "bidirectional"))
    )
    (net (code "96") (name "unconnected-(ARDUINO_DUE1-Pad30)") (class "Default")
      (node (ref "ARDUINO_DUE1") (pin "30") (pinfunction "30_30") (pintype "bidirectional"))
    )
    (net (code "97") (name "unconnected-(ARDUINO_DUE1-Pad31)") (class "Default")
      (node (ref "ARDUINO_DUE1") (pin "31") (pinfunction "31_31") (pintype "bidirectional"))
    )
    (net (code "98") (name "unconnected-(ARDUINO_DUE1-Pad32)") (class "Default")
      (node (ref "ARDUINO_DUE1") (pin "32") (pinfunction "32_32") (pintype "bidirectional"))
    )
    (net (code "99") (name "unconnected-(ARDUINO_DUE1-Pad33)") (class "Default")
      (node (ref "ARDUINO_DUE1") (pin "33") (pinfunction "33_33") (pintype "bidirectional"))
    )
    (net (code "100") (name "unconnected-(ARDUINO_DUE1-Pad34)") (class "Default")
      (node (ref "ARDUINO_DUE1") (pin "34") (pinfunction "34_34") (pintype "bidirectional"))
    )
    (net (code "101") (name "unconnected-(ARDUINO_DUE1-Pad35)") (class "Default")
      (node (ref "ARDUINO_DUE1") (pin "35") (pinfunction "35_35") (pintype "bidirectional"))
    )
    (net (code "102") (name "unconnected-(ARDUINO_DUE1-Pad36)") (class "Default")
      (node (ref "ARDUINO_DUE1") (pin "36") (pinfunction "36_36") (pintype "bidirectional"))
    )
    (net (code "103") (name "unconnected-(ARDUINO_DUE1-Pad37)") (class "Default")
      (node (ref "ARDUINO_DUE1") (pin "37") (pinfunction "37_37") (pintype "bidirectional"))
    )
    (net (code "104") (name "unconnected-(ARDUINO_DUE1-Pad38)") (class "Default")
      (node (ref "ARDUINO_DUE1") (pin "38") (pinfunction "38_38") (pintype "bidirectional"))
    )
    (net (code "105") (name "unconnected-(ARDUINO_DUE1-Pad39)") (class "Default")
      (node (ref "ARDUINO_DUE1") (pin "39") (pinfunction "39_39") (pintype "bidirectional"))
    )
    (net (code "106") (name "unconnected-(ARDUINO_DUE1-Pad40)") (class "Default")
      (node (ref "ARDUINO_DUE1") (pin "40") (pinfunction "40_40") (pintype "bidirectional"))
    )
    (net (code "107") (name "unconnected-(ARDUINO_DUE1-Pad41)") (class "Default")
      (node (ref "ARDUINO_DUE1") (pin "41") (pinfunction "41_41") (pintype "bidirectional"))
    )
    (net (code "108") (name "unconnected-(ARDUINO_DUE1-Pad42)") (class "Default")
      (node (ref "ARDUINO_DUE1") (pin "42") (pinfunction "42_42") (pintype "bidirectional"))
    )
    (net (code "109") (name "unconnected-(ARDUINO_DUE1-Pad43)") (class "Default")
      (node (ref "ARDUINO_DUE1") (pin "43") (pinfunction "43_43") (pintype "bidirectional"))
    )
    (net (code "110") (name "unconnected-(ARDUINO_DUE1-Pad44)") (class "Default")
      (node (ref "ARDUINO_DUE1") (pin "44") (pinfunction "44_44") (pintype "bidirectional"))
    )
    (net (code "111") (name "unconnected-(ARDUINO_DUE1-Pad45)") (class "Default")
      (node (ref "ARDUINO_DUE1") (pin "45") (pinfunction "45_45") (pintype "bidirectional"))
    )
    (net (code "112") (name "unconnected-(ARDUINO_DUE1-Pad46)") (class "Default")
      (node (ref "ARDUINO_DUE1") (pin "46") (pinfunction "46_46") (pintype "bidirectional"))
    )
    (net (code "113") (name "unconnected-(ARDUINO_DUE1-Pad47)") (class "Default")
      (node (ref "ARDUINO_DUE1") (pin "47") (pinfunction "47_47") (pintype "bidirectional"))
    )
    (net (code "114") (name "unconnected-(ARDUINO_DUE1-Pad48)") (class "Default")
      (node (ref "ARDUINO_DUE1") (pin "48") (pinfunction "48_48") (pintype "bidirectional"))
    )
    (net (code "115") (name "unconnected-(ARDUINO_DUE1-Pad49)") (class "Default")
      (node (ref "ARDUINO_DUE1") (pin "49") (pinfunction "49_49") (pintype "bidirectional"))
    )
    (net (code "116") (name "unconnected-(ARDUINO_DUE1-Pad50)") (class "Default")
      (node (ref "ARDUINO_DUE1") (pin "50") (pinfunction "50_50") (pintype "bidirectional"))
    )
    (net (code "117") (name "unconnected-(ARDUINO_DUE1-Pad52)") (class "Default")
      (node (ref "ARDUINO_DUE1") (pin "52") (pinfunction "52_52") (pintype "bidirectional"))
    )
    (net (code "118") (name "unconnected-(ARDUINO_DUE1-PadAREF)") (class "Default")
      (node (ref "ARDUINO_DUE1") (pin "AREF") (pinfunction "AREF_AREF") (pintype "bidirectional"))
    )
    (net (code "119") (name "unconnected-(ARDUINO_DUE1-PadCANRX)") (class "Default")
      (node (ref "ARDUINO_DUE1") (pin "CANRX") (pinfunction "CANRX_CANRX") (pintype "bidirectional"))
    )
    (net (code "120") (name "unconnected-(ARDUINO_DUE1-PadCANTX)") (class "Default")
      (node (ref "ARDUINO_DUE1") (pin "CANTX") (pinfunction "CANTX_CANTX") (pintype "bidirectional"))
    )
    (net (code "121") (name "unconnected-(ARDUINO_DUE1-PadDAC1)") (class "Default")
      (node (ref "ARDUINO_DUE1") (pin "DAC1") (pinfunction "DAC1_DAC1") (pintype "bidirectional"))
    )
    (net (code "122") (name "unconnected-(ARDUINO_DUE1-PadIOREF)") (class "Default")
      (node (ref "ARDUINO_DUE1") (pin "IOREF") (pinfunction "IOREF_IOREF") (pintype "bidirectional"))
    )
    (net (code "123") (name "unconnected-(ARDUINO_DUE1-PadRESET)") (class "Default")
      (node (ref "ARDUINO_DUE1") (pin "RESET") (pinfunction "RESET_RESET") (pintype "bidirectional"))
    )
    (net (code "124") (name "unconnected-(ARDUINO_DUE1-PadSCL1)") (class "Default")
      (node (ref "ARDUINO_DUE1") (pin "SCL1") (pinfunction "SCL1_SCL1") (pintype "bidirectional"))
    )
    (net (code "125") (name "unconnected-(ARDUINO_DUE1-PadSDA1)") (class "Default")
      (node (ref "ARDUINO_DUE1") (pin "SDA1") (pinfunction "SDA1_SDA1") (pintype "bidirectional"))
    )
    (net (code "126") (name "unconnected-(ARDUINO_DUE1-PadVIN)") (class "Default")
      (node (ref "ARDUINO_DUE1") (pin "VIN") (pinfunction "VIN_VIN") (pintype "bidirectional"))
    )
    (net (code "127") (name "unconnected-(ARDUINO_DUE1-RX0<0-Pad0)") (class "Default")
      (node (ref "ARDUINO_DUE1") (pin "0") (pinfunction "RX0<0_0") (pintype "bidirectional"))
    )
    (net (code "128") (name "unconnected-(ARDUINO_DUE1-RX2_17-Pad17)") (class "Default")
      (node (ref "ARDUINO_DUE1") (pin "17") (pinfunction "RX2_17_17") (pintype "bidirectional"))
    )
    (net (code "129") (name "unconnected-(ARDUINO_DUE1-RX3_15-Pad15)") (class "Default")
      (node (ref "ARDUINO_DUE1") (pin "15") (pinfunction "RX3_15_15") (pintype "bidirectional"))
    )
    (net (code "130") (name "unconnected-(ARDUINO_DUE1-SCL_21-Pad21)") (class "Default")
      (node (ref "ARDUINO_DUE1") (pin "21") (pinfunction "SCL_21_21") (pintype "bidirectional"))
    )
    (net (code "131") (name "unconnected-(ARDUINO_DUE1-SDA_20-Pad20)") (class "Default")
      (node (ref "ARDUINO_DUE1") (pin "20") (pinfunction "SDA_20_20") (pintype "bidirectional"))
    )
    (net (code "132") (name "unconnected-(ARDUINO_DUE1-TX0>1-Pad1)") (class "Default")
      (node (ref "ARDUINO_DUE1") (pin "1") (pinfunction "TX0>1_1") (pintype "bidirectional"))
    )
    (net (code "133") (name "unconnected-(ARDUINO_DUE1-TX2_16-Pad16)") (class "Default")
      (node (ref "ARDUINO_DUE1") (pin "16") (pinfunction "TX2_16_16") (pintype "bidirectional"))
    )
    (net (code "134") (name "unconnected-(ARDUINO_DUE1-TX3_14-Pad14)") (class "Default")
      (node (ref "ARDUINO_DUE1") (pin "14") (pinfunction "TX3_14_14") (pintype "bidirectional"))
    )
    (net (code "135") (name "unconnected-(IC3E-O-Pad10)") (class "Default")
      (node (ref "IC3") (pin "10") (pinfunction "O_10") (pintype "output"))
    )
    (net (code "136") (name "unconnected-(IC3F-O-Pad12)") (class "Default")
      (node (ref "IC3") (pin "12") (pinfunction "O_12") (pintype "output"))
    )
  )
)
